# xyz.net
KiCad netlist of a schematic drawn in EAGLE
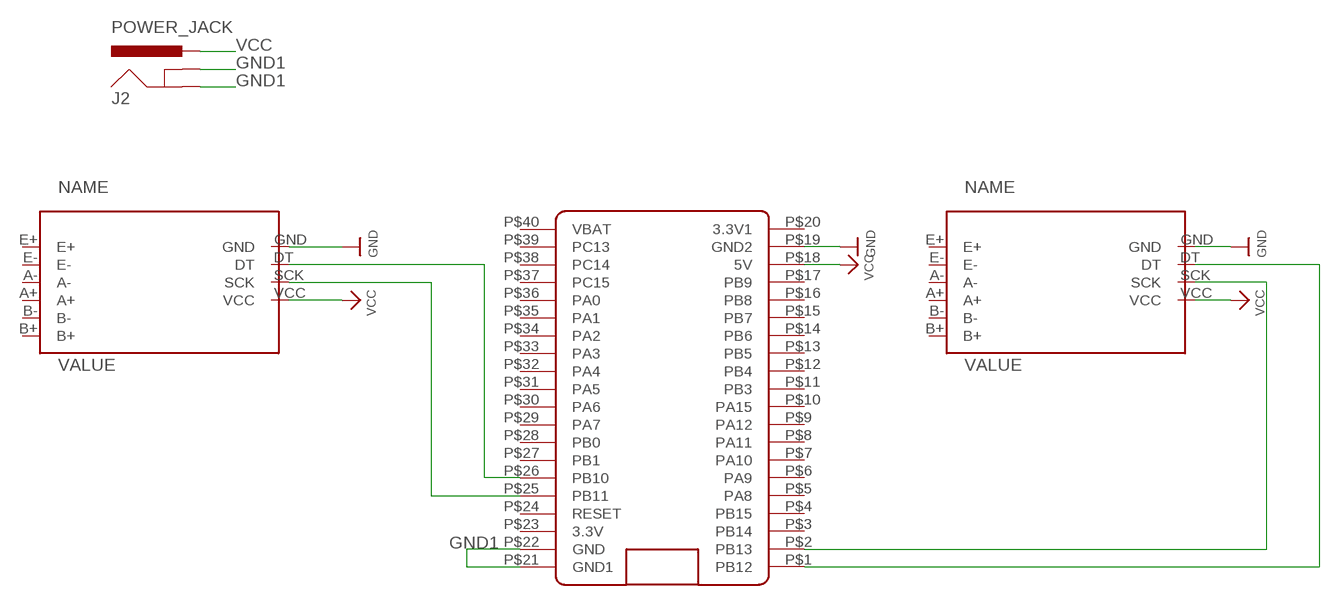
[diagram p0: schematic, sheet 1]

(export (version "E")
  (design (tool "Eeschema 10.0.6"))
  (components
    (comp (ref "J2")
      (value "POWER_JACK")
      (footprint "eagle-import:POWER_JACK")
      (fields (field (name "MPN") "PJ-202A"))
      (libsource (lib "eagle-import") (part "POWER_JACK"))
    )
    (comp (ref "U$1")
      (value "HX711A")
      (footprint "eagle-import:HX711")
      (libsource (lib "eagle-import") (part "HX711A"))
    )
    (comp (ref "U$2")
      (value "HX711A")
      (footprint "eagle-import:HX711")
      (libsource (lib "eagle-import") (part "HX711A"))
    )
    (comp (ref "U$3")
      (value "BLUE_PILL")
      (footprint "eagle-import:BLUE_PILL")
      (libsource (lib "eagle-import") (part "BLUE_PILL"))
    )
  )
  (nets
    (net (code "1") (name "/GND1") (class "Default")
      (node (ref "J2") (pin "GNDBREAK") (pinfunction "GNDBREAK_GNDBREAK") (pintype "bidirectional"))
      (node (ref "U$3") (pin "P$21") (pinfunction "GND1_P$21") (pintype "power_in"))
      (node (ref "U$3") (pin "P$22") (pinfunction "GND_P$22") (pintype "bidirectional"))
    )
    (net (code "2") (name "GND") (class "Default")
      (node (ref "U$1") (pin "GND") (pinfunction "GND_GND") (pintype "bidirectional"))
      (node (ref "U$2") (pin "GND") (pinfunction "GND_GND") (pintype "bidirectional"))
      (node (ref "U$3") (pin "P$19") (pinfunction "GND2_P$19") (pintype "bidirectional"))
    )
    (net (code "3") (name "Net-(U$3-PB10)") (class "Default")
      (node (ref "U$1") (pin "DT") (pinfunction "DT_DT") (pintype "bidirectional"))
      (node (ref "U$3") (pin "P$26") (pinfunction "PB10_P$26") (pintype "bidirectional"))
    )
    (net (code "4") (name "Net-(U$3-PB11)") (class "Default")
      (node (ref "U$1") (pin "SCK") (pinfunction "SCK_SCK") (pintype "bidirectional"))
      (node (ref "U$3") (pin "P$25") (pinfunction "PB11_P$25") (pintype "bidirectional"))
    )
    (net (code "5") (name "Net-(U$3-PB12)") (class "Default")
      (node (ref "U$2") (pin "DT") (pinfunction "DT_DT") (pintype "bidirectional"))
      (node (ref "U$3") (pin "P$1") (pinfunction "PB12_P$1") (pintype "bidirectional"))
    )
    (net (code "6") (name "Net-(U$3-PB13)") (class "Default")
      (node (ref "U$2") (pin "SCK") (pinfunction "SCK_SCK") (pintype "bidirectional"))
      (node (ref "U$3") (pin "P$2") (pinfunction "PB13_P$2") (pintype "bidirectional"))
    )
    (net (code "7") (name "VCC") (class "Default")
      (node (ref "J2") (pin "PWR") (pinfunction "PWR_PWR") (pintype "bidirectional"))
      (node (ref "U$1") (pin "VCC") (pinfunction "VCC_VCC") (pintype "bidirectional"))
      (node (ref "U$2") (pin "VCC") (pinfunction "VCC_VCC") (pintype "bidirectional"))
      (node (ref "U$3") (pin "P$18") (pinfunction "5V_P$18") (pintype "bidirectional"))
    )
    (net (code "8") (name "unconnected-(J2-PadGND)") (class "Default")
      (node (ref "J2") (pin "GND") (pinfunction "GND_GND") (pintype "bidirectional"))
    )
    (net (code "9") (name "unconnected-(U$1-PadA+)") (class "Default")
      (node (ref "U$1") (pin "A+") (pinfunction "A+_A+") (pintype "bidirectional"))
    )
    (net (code "10") (name "unconnected-(U$1-PadA-)") (class "Default")
      (node (ref "U$1") (pin "A-") (pinfunction "A-_A-") (pintype "bidirectional"))
    )
    (net (code "11") (name "unconnected-(U$1-PadB+)") (class "Default")
      (node (ref "U$1") (pin "B+") (pinfunction "B+_B+") (pintype "bidirectional"))
    )
    (net (code "12") (name "unconnected-(U$1-PadB-)") (class "Default")
      (node (ref "U$1") (pin "B-") (pinfunction "B-_B-") (pintype "bidirectional"))
    )
    (net (code "13") (name "unconnected-(U$1-PadE+)") (class "Default")
      (node (ref "U$1") (pin "E+") (pinfunction "E+_E+") (pintype "bidirectional"))
    )
    (net (code "14") (name "unconnected-(U$1-PadE-)") (class "Default")
      (node (ref "U$1") (pin "E-") (pinfunction "E-_E-") (pintype "bidirectional"))
    )
    (net (code "15") (name "unconnected-(U$2-PadA+)") (class "Default")
      (node (ref "U$2") (pin "A+") (pinfunction "A+_A+") (pintype "bidirectional"))
    )
    (net (code "16") (name "unconnected-(U$2-PadA-)") (class "Default")
      (node (ref "U$2") (pin "A-") (pinfunction "A-_A-") (pintype "bidirectional"))
    )
    (net (code "17") (name "unconnected-(U$2-PadB+)") (class "Default")
      (node (ref "U$2") (pin "B+") (pinfunction "B+_B+") (pintype "bidirectional"))
    )
    (net (code "18") (name "unconnected-(U$2-PadB-)") (class "Default")
      (node (ref "U$2") (pin "B-") (pinfunction "B-_B-") (pintype "bidirectional"))
    )
    (net (code "19") (name "unconnected-(U$2-PadE+)") (class "Default")
      (node (ref "U$2") (pin "E+") (pinfunction "E+_E+") (pintype "bidirectional"))
    )
    (net (code "20") (name "unconnected-(U$2-PadE-)") (class "Default")
      (node (ref "U$2") (pin "E-") (pinfunction "E-_E-") (pintype "bidirectional"))
    )
    (net (code "21") (name "unconnected-(U$3-3.3V-PadP$23)") (class "Default")
      (node (ref "U$3") (pin "P$23") (pinfunction "3.3V_P$23") (pintype "bidirectional"))
    )
    (net (code "22") (name "unconnected-(U$3-3.3V1-PadP$20)") (class "Default")
      (node (ref "U$3") (pin "P$20") (pinfunction "3.3V1_P$20") (pintype "bidirectional"))
    )
    (net (code "23") (name "unconnected-(U$3-PA0-PadP$36)") (class "Default")
      (node (ref "U$3") (pin "P$36") (pinfunction "PA0_P$36") (pintype "bidirectional"))
    )
    (net (code "24") (name "unconnected-(U$3-PA1-PadP$35)") (class "Default")
      (node (ref "U$3") (pin "P$35") (pinfunction "PA1_P$35") (pintype "bidirectional"))
    )
    (net (code "25") (name "unconnected-(U$3-PA2-PadP$34)") (class "Default")
      (node (ref "U$3") (pin "P$34") (pinfunction "PA2_P$34") (pintype "bidirectional"))
    )
    (net (code "26") (name "unconnected-(U$3-PA3-PadP$33)") (class "Default")
      (node (ref "U$3") (pin "P$33") (pinfunction "PA3_P$33") (pintype "bidirectional"))
    )
    (net (code "27") (name "unconnected-(U$3-PA4-PadP$32)") (class "Default")
      (node (ref "U$3") (pin "P$32") (pinfunction "PA4_P$32") (pintype "bidirectional"))
    )
    (net (code "28") (name "unconnected-(U$3-PA5-PadP$31)") (class "Default")
      (node (ref "U$3") (pin "P$31") (pinfunction "PA5_P$31") (pintype "bidirectional"))
    )
    (net (code "29") (name "unconnected-(U$3-PA6-PadP$30)") (class "Default")
      (node (ref "U$3") (pin "P$30") (pinfunction "PA6_P$30") (pintype "bidirectional"))
    )
    (net (code "30") (name "unconnected-(U$3-PA7-PadP$29)") (class "Default")
      (node (ref "U$3") (pin "P$29") (pinfunction "PA7_P$29") (pintype "bidirectional"))
    )
    (net (code "31") (name "unconnected-(U$3-PA8-PadP$5)") (class "Default")
      (node (ref "U$3") (pin "P$5") (pinfunction "PA8_P$5") (pintype "bidirectional"))
    )
    (net (code "32") (name "unconnected-(U$3-PA9-PadP$6)") (class "Default")
      (node (ref "U$3") (pin "P$6") (pinfunction "PA9_P$6") (pintype "bidirectional"))
    )
    (net (code "33") (name "unconnected-(U$3-PA10-PadP$7)") (class "Default")
      (node (ref "U$3") (pin "P$7") (pinfunction "PA10_P$7") (pintype "bidirectional"))
    )
    (net (code "34") (name "unconnected-(U$3-PA11-PadP$8)") (class "Default")
      (node (ref "U$3") (pin "P$8") (pinfunction "PA11_P$8") (pintype "bidirectional"))
    )
    (net (code "35") (name "unconnected-(U$3-PA12-PadP$9)") (class "Default")
      (node (ref "U$3") (pin "P$9") (pinfunction "PA12_P$9") (pintype "bidirectional"))
    )
    (net (code "36") (name "unconnected-(U$3-PA15-PadP$10)") (class "Default")
      (node (ref "U$3") (pin "P$10") (pinfunction "PA15_P$10") (pintype "bidirectional"))
    )
    (net (code "37") (name "unconnected-(U$3-PB0-PadP$28)") (class "Default")
      (node (ref "U$3") (pin "P$28") (pinfunction "PB0_P$28") (pintype "bidirectional"))
    )
    (net (code "38") (name "unconnected-(U$3-PB1-PadP$27)") (class "Default")
      (node (ref "U$3") (pin "P$27") (pinfunction "PB1_P$27") (pintype "bidirectional"))
    )
    (net (code "39") (name "unconnected-(U$3-PB3-PadP$11)") (class "Default")
      (node (ref "U$3") (pin "P$11") (pinfunction "PB3_P$11") (pintype "bidirectional"))
    )
    (net (code "40") (name "unconnected-(U$3-PB4-PadP$12)") (class "Default")
      (node (ref "U$3") (pin "P$12") (pinfunction "PB4_P$12") (pintype "bidirectional"))
    )
    (net (code "41") (name "unconnected-(U$3-PB5-PadP$13)") (class "Default")
      (node (ref "U$3") (pin "P$13") (pinfunction "PB5_P$13") (pintype "bidirectional"))
    )
    (net (code "42") (name "unconnected-(U$3-PB6-PadP$14)") (class "Default")
      (node (ref "U$3") (pin "P$14") (pinfunction "PB6_P$14") (pintype "bidirectional"))
    )
    (net (code "43") (name "unconnected-(U$3-PB7-PadP$15)") (class "Default")
      (node (ref "U$3") (pin "P$15") (pinfunction "PB7_P$15") (pintype "bidirectional"))
    )
    (net (code "44") (name "unconnected-(U$3-PB8-PadP$16)") (class "Default")
      (node (ref "U$3") (pin "P$16") (pinfunction "PB8_P$16") (pintype "bidirectional"))
    )
    (net (code "45") (name "unconnected-(U$3-PB9-PadP$17)") (class "Default")
      (node (ref "U$3") (pin "P$17") (pinfunction "PB9_P$17") (pintype "bidirectional"))
    )
    (net (code "46") (name "unconnected-(U$3-PB14-PadP$3)") (class "Default")
      (node (ref "U$3") (pin "P$3") (pinfunction "PB14_P$3") (pintype "bidirectional"))
    )
    (net (code "47") (name "unconnected-(U$3-PB15-PadP$4)") (class "Default")
      (node (ref "U$3") (pin "P$4") (pinfunction "PB15_P$4") (pintype "bidirectional"))
    )
    (net (code "48") (name "unconnected-(U$3-PC13-PadP$39)") (class "Default")
      (node (ref "U$3") (pin "P$39") (pinfunction "PC13_P$39") (pintype "bidirectional"))
    )
    (net (code "49") (name "unconnected-(U$3-PC14-PadP$38)") (class "Default")
      (node (ref "U$3") (pin "P$38") (pinfunction "PC14_P$38") (pintype "bidirectional"))
    )
    (net (code "50") (name "unconnected-(U$3-PC15-PadP$37)") (class "Default")
      (node (ref "U$3") (pin "P$37") (pinfunction "PC15_P$37") (pintype "bidirectional"))
    )
    (net (code "51") (name "unconnected-(U$3-RESET-PadP$24)") (class "Default")
      (node (ref "U$3") (pin "P$24") (pinfunction "RESET_P$24") (pintype "bidirectional"))
    )
    (net (code "52") (name "unconnected-(U$3-VBAT-PadP$40)") (class "Default")
      (node (ref "U$3") (pin "P$40") (pinfunction "VBAT_P$40") (pintype "bidirectional"))
    )
  )
)
